# U_I_Meter_Bottom.net
KiCad netlist of a schematic drawn in Altium Designer
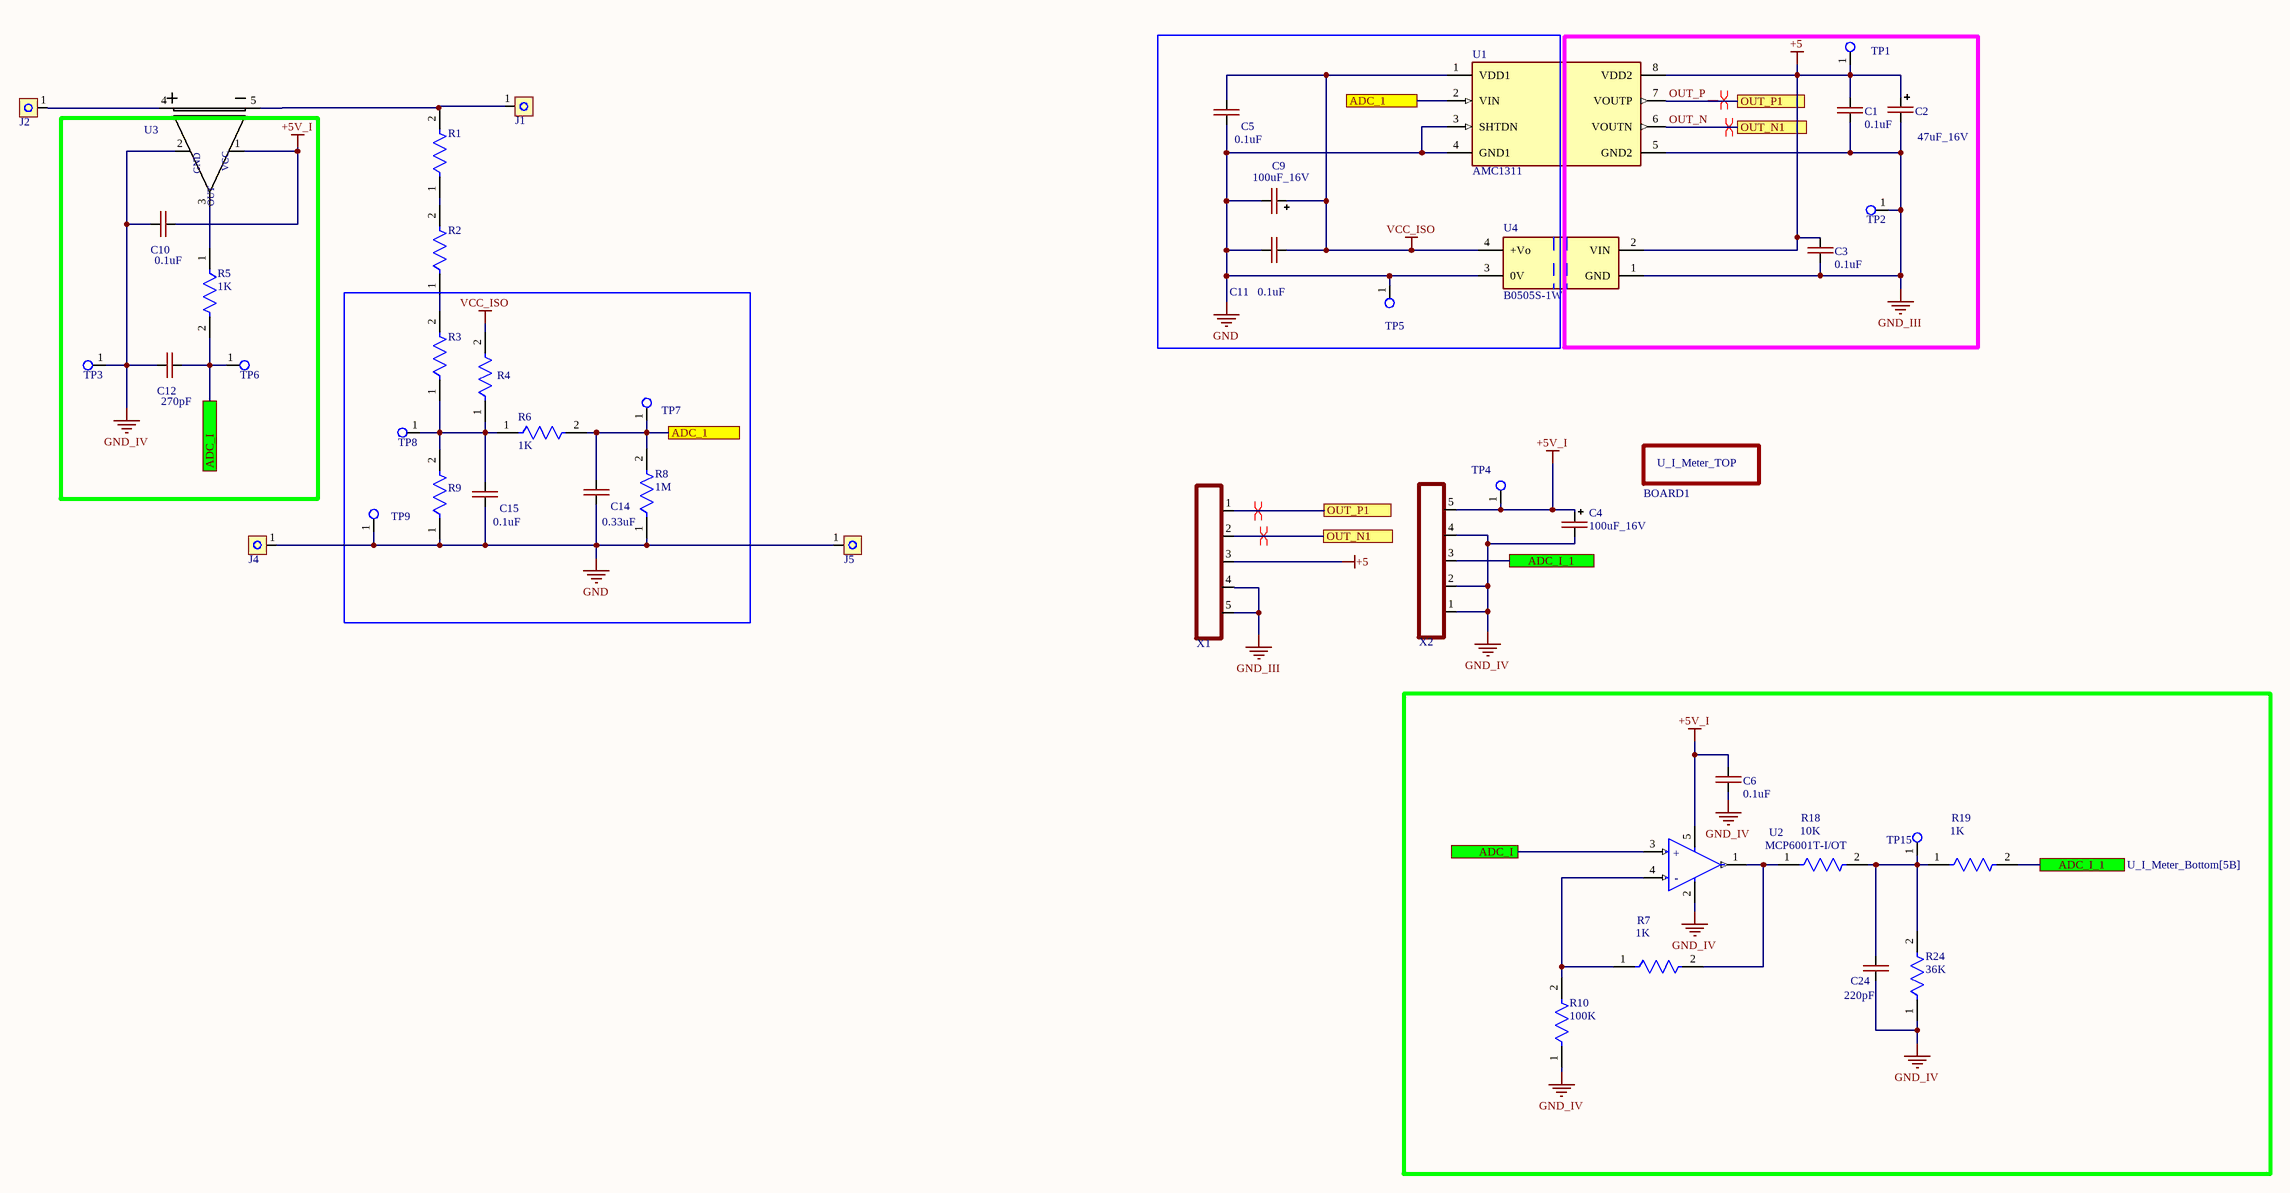
[diagram p0: U_I_Meter_Bottom.SchDoc]

(export (version "E")
  (design (tool "Eeschema 10.0.6"))
  (components
    (comp (ref "BOARD1")
      (value "U_I_Meter_TOP")
      (footprint "U_I_Meter_TOP")
      (libsource (lib "U_I_Meter_TOP") (part "U_I_Meter_TOP"))
    )
    (comp (ref "C1")
      (value "0.1uF")
      (footprint "CAP-0805")
      (libsource (lib "PASSIVE_COMPONENTS") (part "CAP-NON-POLAR"))
    )
    (comp (ref "C2")
      (value "47uF_16V")
      (footprint "CAP-TAN-D")
      (libsource (lib "PASSIVE_COMPONENTS") (part "CAP-POLAR"))
    )
    (comp (ref "C3")
      (value "0.1uF")
      (footprint "CAP-0805")
      (libsource (lib "PASSIVE_COMPONENTS") (part "CAP-NON-POLAR"))
    )
    (comp (ref "C4")
      (value "100uF_16V")
      (footprint "CAP-TAN-D")
      (libsource (lib "PASSIVE_COMPONENTS") (part "CAP_POL_SMD"))
    )
    (comp (ref "C5")
      (value "0.1uF")
      (footprint "CAP-0805")
      (libsource (lib "PASSIVE_COMPONENTS") (part "CAP-NON-POLAR"))
    )
    (comp (ref "C6")
      (value "0.1uF")
      (footprint "CAP-0805")
      (libsource (lib "PASSIVE_COMPONENTS") (part "CAP-NON-POLAR"))
    )
    (comp (ref "C9")
      (value "100uF_16V")
      (footprint "CAP-TAN-D")
      (libsource (lib "PASSIVE_COMPONENTS") (part "CAP_POL_SMD"))
    )
    (comp (ref "C10")
      (value "0.1uF")
      (footprint "CAP-0805")
      (libsource (lib "PASSIVE_COMPONENTS") (part "CAP-NON-POLAR"))
    )
    (comp (ref "C11")
      (value "0.1uF")
      (footprint "CAP-0805")
      (libsource (lib "PASSIVE_COMPONENTS") (part "CAP-NON-POLAR"))
    )
    (comp (ref "C12")
      (value "270pF")
      (footprint "CAP-0805")
      (libsource (lib "PASSIVE_COMPONENTS") (part "CAP-NON-POLAR"))
    )
    (comp (ref "C14")
      (value "0.33uF")
      (footprint "CAP-0805")
      (libsource (lib "PASSIVE_COMPONENTS") (part "CAP-NON-POLAR"))
    )
    (comp (ref "C15")
      (value "0.1uF")
      (footprint "CAP-0805")
      (libsource (lib "PASSIVE_COMPONENTS") (part "CAP-NON-POLAR"))
    )
    (comp (ref "C24")
      (value "220pF")
      (footprint "CAP-0805")
      (libsource (lib "PASSIVE_COMPONENTS") (part "CAP-NON-POLAR"))
    )
    (comp (ref "J1")
      (value "MG_136_HT")
      (footprint "Conn_MEIGAN_MG136HT")
      (libsource (lib "") (part "Connector_MEIGAN_MG136HT_1"))
    )
    (comp (ref "J2")
      (value "MG_136_HT")
      (footprint "Conn_MEIGAN_MG136HT")
      (libsource (lib "Connectors") (part "Connector_MEIGAN_MG136HT"))
    )
    (comp (ref "J4")
      (value "MG_136_HT")
      (footprint "Conn_MEIGAN_MG136HT")
      (libsource (lib "Connectors") (part "Connector_MEIGAN_MG136HT"))
    )
    (comp (ref "J5")
      (value "MG_136_HT")
      (footprint "Conn_MEIGAN_MG136HT")
      (libsource (lib "") (part "Connector_MEIGAN_MG136HT_1"))
    )
    (comp (ref "R1")
      (value "~")
      (footprint "RES-2512")
      (libsource (lib "PASSIVE_COMPONENTS") (part "RES-CONST"))
    )
    (comp (ref "R2")
      (value "~")
      (footprint "RES-2512")
      (libsource (lib "PASSIVE_COMPONENTS") (part "RES-CONST"))
    )
    (comp (ref "R3")
      (value "~")
      (footprint "RES-2512")
      (libsource (lib "PASSIVE_COMPONENTS") (part "RES-CONST"))
    )
    (comp (ref "R4")
      (value "~")
      (footprint "RES-0805")
      (libsource (lib "PASSIVE_COMPONENTS") (part "RES-CONST"))
    )
    (comp (ref "R5")
      (value "1K")
      (footprint "RES-0805")
      (libsource (lib "PASSIVE_COMPONENTS") (part "RES-CONST"))
    )
    (comp (ref "R6")
      (value "1K")
      (footprint "RES-0805")
      (libsource (lib "PASSIVE_COMPONENTS") (part "RES-CONST"))
    )
    (comp (ref "R7")
      (value "1K")
      (footprint "RES-0805")
      (description "10K")
      (libsource (lib "PASSIVE_COMPONENTS") (part "RES-CONST"))
    )
    (comp (ref "R8")
      (value "1M")
      (footprint "RES-0805")
      (libsource (lib "PASSIVE_COMPONENTS") (part "RES-CONST"))
    )
    (comp (ref "R9")
      (value "RES_1210")
      (footprint "RES_SMD_1210_IPC_B")
      (libsource (lib "PASSIVE_COMPONENTS") (part "RES_1210"))
    )
    (comp (ref "R10")
      (value "100K")
      (footprint "RES-0805")
      (libsource (lib "PASSIVE_COMPONENTS") (part "RES-CONST"))
    )
    (comp (ref "R18")
      (value "10K")
      (footprint "RES-0805")
      (libsource (lib "PASSIVE_COMPONENTS") (part "RES-CONST"))
    )
    (comp (ref "R19")
      (value "1K")
      (footprint "RES-0805")
      (description "10K")
      (libsource (lib "PASSIVE_COMPONENTS") (part "RES-CONST"))
    )
    (comp (ref "R24")
      (value "36K")
      (footprint "RES-0805")
      (libsource (lib "PASSIVE_COMPONENTS") (part "RES-CONST"))
    )
    (comp (ref "TP1")
      (value "Test_Point_PCB")
      (footprint "Test_Point")
      (description "Test_Point")
      (libsource (lib "Connectors") (part "TP_PCB?"))
    )
    (comp (ref "TP2")
      (value "Test_Point_PCB")
      (footprint "Test_Point")
      (description "Test_Point")
      (libsource (lib "Connectors") (part "TP_PCB?"))
    )
    (comp (ref "TP3")
      (value "Test_Point_PCB")
      (footprint "Test_Point")
      (description "Test_Point")
      (libsource (lib "Connectors") (part "TP_PCB?"))
    )
    (comp (ref "TP4")
      (value "Test_Point_PCB")
      (footprint "Test_Point")
      (description "Test_Point")
      (libsource (lib "Connectors") (part "TP_PCB?"))
    )
    (comp (ref "TP5")
      (value "Test_Point_PCB")
      (footprint "Pin_Test_Point(Pink)")
      (description "Test_Point")
      (libsource (lib "Connectors") (part "TP_PCB?"))
    )
    (comp (ref "TP6")
      (value "Test_Point_PCB")
      (footprint "Test_Point")
      (description "Test_Point")
      (libsource (lib "Connectors") (part "TP_PCB?"))
    )
    (comp (ref "TP7")
      (value "Test_Point_PCB")
      (footprint "Test_Point")
      (description "Test_Point")
      (libsource (lib "Connectors") (part "TP_PCB?"))
    )
    (comp (ref "TP8")
      (value "Test_Point_PCB")
      (footprint "Test_Point")
      (description "Test_Point")
      (libsource (lib "Connectors") (part "TP_PCB?"))
    )
    (comp (ref "TP9")
      (value "Test_Point_PCB")
      (footprint "Test_Point")
      (description "Test_Point")
      (libsource (lib "Connectors") (part "TP_PCB?"))
    )
    (comp (ref "TP15")
      (value "Test_Point_PCB")
      (footprint "Test_Point")
      (description "Test_Point")
      (libsource (lib "Connectors") (part "TP_PCB?"))
    )
    (comp (ref "U1")
      (value "AMC1311")
      (footprint "FP-DWV0008A-MFG")
      (libsource (lib "Integrated_Circuts") (part "AMC1311"))
    )
    (comp (ref "U2")
      (value "MCP6001T-I/OT")
      (footprint "SOT-23-5")
      (description "IC OPAMP GP 1 CIRCUIT SOT23-5")
      (fields (field (name "VOLTAGE") "6V"))
      (libsource (lib "Integrated_Circuts") (part "MCP6001T"))
    )
    (comp (ref "U3")
      (value "ACS758")
      (footprint "ACS758-100")
      (libsource (lib "Integrated_Circuts") (part "ACS758"))
    )
    (comp (ref "U4")
      (value "B0505S-1W")
      (footprint "B0505S-1W")
      (libsource (lib "Integrated_Circuts") (part "B0505S-1W"))
    )
    (comp (ref "X1")
      (value "CONN-5-PIN")
      (footprint "CONN-PLS-5-2.54mm")
      (libsource (lib "") (part "CONN-5-PIN_1"))
    )
    (comp (ref "X2")
      (value "CONN-5-PIN")
      (footprint "CONN-PLS-5-2.54mm")
      (libsource (lib "PLS-5__") (part "CONN-5-PIN"))
    )
  )
  (nets
    (net (code "1") (name "+5") (class "Default")
      (node (ref "C1") (pin "1") (pinfunction "1_1") (pintype "passive"))
      (node (ref "C2") (pin "1") (pinfunction "+_1") (pintype "passive"))
      (node (ref "C3") (pin "1") (pinfunction "1_1") (pintype "passive"))
      (node (ref "TP1") (pin "1") (pinfunction "G9_1") (pintype "passive"))
      (node (ref "U1") (pin "8") (pinfunction "VDD2_8") (pintype "power_in"))
      (node (ref "U4") (pin "2") (pinfunction "VIN_2") (pintype "power_in"))
      (node (ref "X1") (pin "3") (pinfunction "3_3") (pintype "passive"))
    )
    (net (code "2") (name "+5V_I") (class "Default")
      (node (ref "C10") (pin "2") (pinfunction "2_2") (pintype "passive"))
      (node (ref "C4") (pin "1") (pinfunction "+_1") (pintype "passive"))
      (node (ref "C6") (pin "2") (pinfunction "2_2") (pintype "passive"))
      (node (ref "TP4") (pin "1") (pinfunction "G9_1") (pintype "passive"))
      (node (ref "U2") (pin "5") (pinfunction "VDD_5") (pintype "power_in"))
      (node (ref "U3") (pin "1") (pinfunction "+VCC_1") (pintype "passive"))
      (node (ref "X2") (pin "5") (pinfunction "5_5") (pintype "passive"))
    )
    (net (code "3") (name "/ADC_1") (class "Default")
      (node (ref "C14") (pin "2") (pinfunction "2_2") (pintype "passive"))
      (node (ref "R6") (pin "2") (pinfunction "2_2") (pintype "passive"))
      (node (ref "R8") (pin "2") (pinfunction "2_2") (pintype "passive"))
      (node (ref "TP7") (pin "1") (pinfunction "G9_1") (pintype "passive"))
      (node (ref "U1") (pin "2") (pinfunction "VIN_2") (pintype "input"))
    )
    (net (code "4") (name "/ADC_I") (class "Default")
      (node (ref "C12") (pin "2") (pinfunction "2_2") (pintype "passive"))
      (node (ref "R5") (pin "2") (pinfunction "2_2") (pintype "passive"))
      (node (ref "TP6") (pin "1") (pinfunction "G9_1") (pintype "passive"))
      (node (ref "U2") (pin "3") (pinfunction "VIN+_3") (pintype "input"))
    )
    (net (code "5") (name "/ADC_I_1") (class "Default")
      (node (ref "R19") (pin "2") (pinfunction "2_2") (pintype "passive"))
      (node (ref "X2") (pin "3") (pinfunction "3_3") (pintype "passive"))
    )
    (net (code "6") (name "/OUT_N") (class "Default")
      (node (ref "U1") (pin "6") (pinfunction "VOUTN_6") (pintype "output"))
      (node (ref "X1") (pin "2") (pinfunction "2_2") (pintype "passive"))
    )
    (net (code "7") (name "/OUT_P") (class "Default")
      (node (ref "U1") (pin "7") (pinfunction "VOUTP_7") (pintype "output"))
      (node (ref "X1") (pin "1") (pinfunction "1_1") (pintype "passive"))
    )
    (net (code "8") (name "GND") (class "Default")
      (node (ref "C11") (pin "2") (pinfunction "2_2") (pintype "passive"))
      (node (ref "C14") (pin "1") (pinfunction "1_1") (pintype "passive"))
      (node (ref "C15") (pin "1") (pinfunction "1_1") (pintype "passive"))
      (node (ref "C5") (pin "1") (pinfunction "1_1") (pintype "passive"))
      (node (ref "C9") (pin "2") (pinfunction "-_2") (pintype "passive"))
      (node (ref "J4") (pin "1") (pinfunction "17_1") (pintype "passive"))
      (node (ref "J5") (pin "1") (pinfunction "17_1") (pintype "passive"))
      (node (ref "R8") (pin "1") (pinfunction "1_1") (pintype "passive"))
      (node (ref "R9") (pin "1") (pinfunction "1_1") (pintype "passive"))
      (node (ref "TP5") (pin "1") (pinfunction "G9_1") (pintype "passive"))
      (node (ref "TP9") (pin "1") (pinfunction "G9_1") (pintype "passive"))
      (node (ref "U1") (pin "3") (pinfunction "SHTDN_3") (pintype "input"))
      (node (ref "U1") (pin "4") (pinfunction "GND1_4") (pintype "power_in"))
      (node (ref "U4") (pin "3") (pinfunction "0V_3") (pintype "power_in"))
    )
    (net (code "9") (name "GND_III") (class "Default")
      (node (ref "C1") (pin "2") (pinfunction "2_2") (pintype "passive"))
      (node (ref "C2") (pin "2") (pinfunction "-_2") (pintype "passive"))
      (node (ref "C3") (pin "2") (pinfunction "2_2") (pintype "passive"))
      (node (ref "TP2") (pin "1") (pinfunction "G9_1") (pintype "passive"))
      (node (ref "U1") (pin "5") (pinfunction "GND2_5") (pintype "power_in"))
      (node (ref "U4") (pin "1") (pinfunction "GND_1") (pintype "power_in"))
      (node (ref "X1") (pin "4") (pinfunction "4_4") (pintype "passive"))
      (node (ref "X1") (pin "5") (pinfunction "5_5") (pintype "passive"))
    )
    (net (code "10") (name "GND_IV") (class "Default")
      (node (ref "C10") (pin "1") (pinfunction "1_1") (pintype "passive"))
      (node (ref "C12") (pin "1") (pinfunction "1_1") (pintype "passive"))
      (node (ref "C24") (pin "1") (pinfunction "1_1") (pintype "passive"))
      (node (ref "C4") (pin "2") (pinfunction "-_2") (pintype "passive"))
      (node (ref "C6") (pin "1") (pinfunction "1_1") (pintype "passive"))
      (node (ref "R10") (pin "1") (pinfunction "1_1") (pintype "passive"))
      (node (ref "R24") (pin "1") (pinfunction "1_1") (pintype "passive"))
      (node (ref "TP3") (pin "1") (pinfunction "G9_1") (pintype "passive"))
      (node (ref "U2") (pin "2") (pinfunction "VSS_2") (pintype "power_in"))
      (node (ref "U3") (pin "2") (pinfunction "GND_2") (pintype "passive"))
      (node (ref "X2") (pin "1") (pinfunction "1_1") (pintype "passive"))
      (node (ref "X2") (pin "2") (pinfunction "2_2") (pintype "passive"))
      (node (ref "X2") (pin "4") (pinfunction "4_4") (pintype "passive"))
    )
    (net (code "11") (name "Net-(J1-17)") (class "Default")
      (node (ref "J1") (pin "1") (pinfunction "17_1") (pintype "passive"))
      (node (ref "R1") (pin "2") (pinfunction "2_2") (pintype "passive"))
      (node (ref "U3") (pin "5") (pinfunction "-IP_5") (pintype "passive"))
    )
    (net (code "12") (name "Net-(J2-17)") (class "Default")
      (node (ref "J2") (pin "1") (pinfunction "17_1") (pintype "passive"))
      (node (ref "U3") (pin "4") (pinfunction "+IP_4") (pintype "passive"))
    )
    (net (code "13") (name "Net-(R1-Pad1)") (class "Default")
      (node (ref "R1") (pin "1") (pinfunction "1_1") (pintype "passive"))
      (node (ref "R2") (pin "2") (pinfunction "2_2") (pintype "passive"))
    )
    (net (code "14") (name "Net-(R2-Pad1)") (class "Default")
      (node (ref "R2") (pin "1") (pinfunction "1_1") (pintype "passive"))
      (node (ref "R3") (pin "2") (pinfunction "2_2") (pintype "passive"))
    )
    (net (code "15") (name "Net-(TP8-G9)") (class "Default")
      (node (ref "C15") (pin "2") (pinfunction "2_2") (pintype "passive"))
      (node (ref "R3") (pin "1") (pinfunction "1_1") (pintype "passive"))
      (node (ref "R4") (pin "1") (pinfunction "1_1") (pintype "passive"))
      (node (ref "R6") (pin "1") (pinfunction "1_1") (pintype "passive"))
      (node (ref "R9") (pin "2") (pinfunction "2_2") (pintype "passive"))
      (node (ref "TP8") (pin "1") (pinfunction "G9_1") (pintype "passive"))
    )
    (net (code "16") (name "Net-(TP15-G9)") (class "Default")
      (node (ref "C24") (pin "2") (pinfunction "2_2") (pintype "passive"))
      (node (ref "R18") (pin "2") (pinfunction "2_2") (pintype "passive"))
      (node (ref "R19") (pin "1") (pinfunction "1_1") (pintype "passive"))
      (node (ref "R24") (pin "2") (pinfunction "2_2") (pintype "passive"))
      (node (ref "TP15") (pin "1") (pinfunction "G9_1") (pintype "passive"))
    )
    (net (code "17") (name "Net-(U2-VIN-)") (class "Default")
      (node (ref "R10") (pin "2") (pinfunction "2_2") (pintype "passive"))
      (node (ref "R7") (pin "1") (pinfunction "1_1") (pintype "passive"))
      (node (ref "U2") (pin "4") (pinfunction "VIN-_4") (pintype "input"))
    )
    (net (code "18") (name "Net-(U2-VOUT)") (class "Default")
      (node (ref "R18") (pin "1") (pinfunction "1_1") (pintype "passive"))
      (node (ref "R7") (pin "2") (pinfunction "2_2") (pintype "passive"))
      (node (ref "U2") (pin "1") (pinfunction "VOUT_1") (pintype "output"))
    )
    (net (code "19") (name "Net-(U3-OUT)") (class "Default")
      (node (ref "R5") (pin "1") (pinfunction "1_1") (pintype "passive"))
      (node (ref "U3") (pin "3") (pinfunction "OUT_3") (pintype "passive"))
    )
    (net (code "20") (name "VCC_ISO") (class "Default")
      (node (ref "C11") (pin "1") (pinfunction "1_1") (pintype "passive"))
      (node (ref "C5") (pin "2") (pinfunction "2_2") (pintype "passive"))
      (node (ref "C9") (pin "1") (pinfunction "+_1") (pintype "passive"))
      (node (ref "R4") (pin "2") (pinfunction "2_2") (pintype "passive"))
      (node (ref "U1") (pin "1") (pinfunction "VDD1_1") (pintype "power_in"))
      (node (ref "U4") (pin "4") (pinfunction "+Vo_4") (pintype "power_in"))
    )
  )
)
